# RGB_CCM.net
KiCad netlist of a schematic drawn in Altium Designer
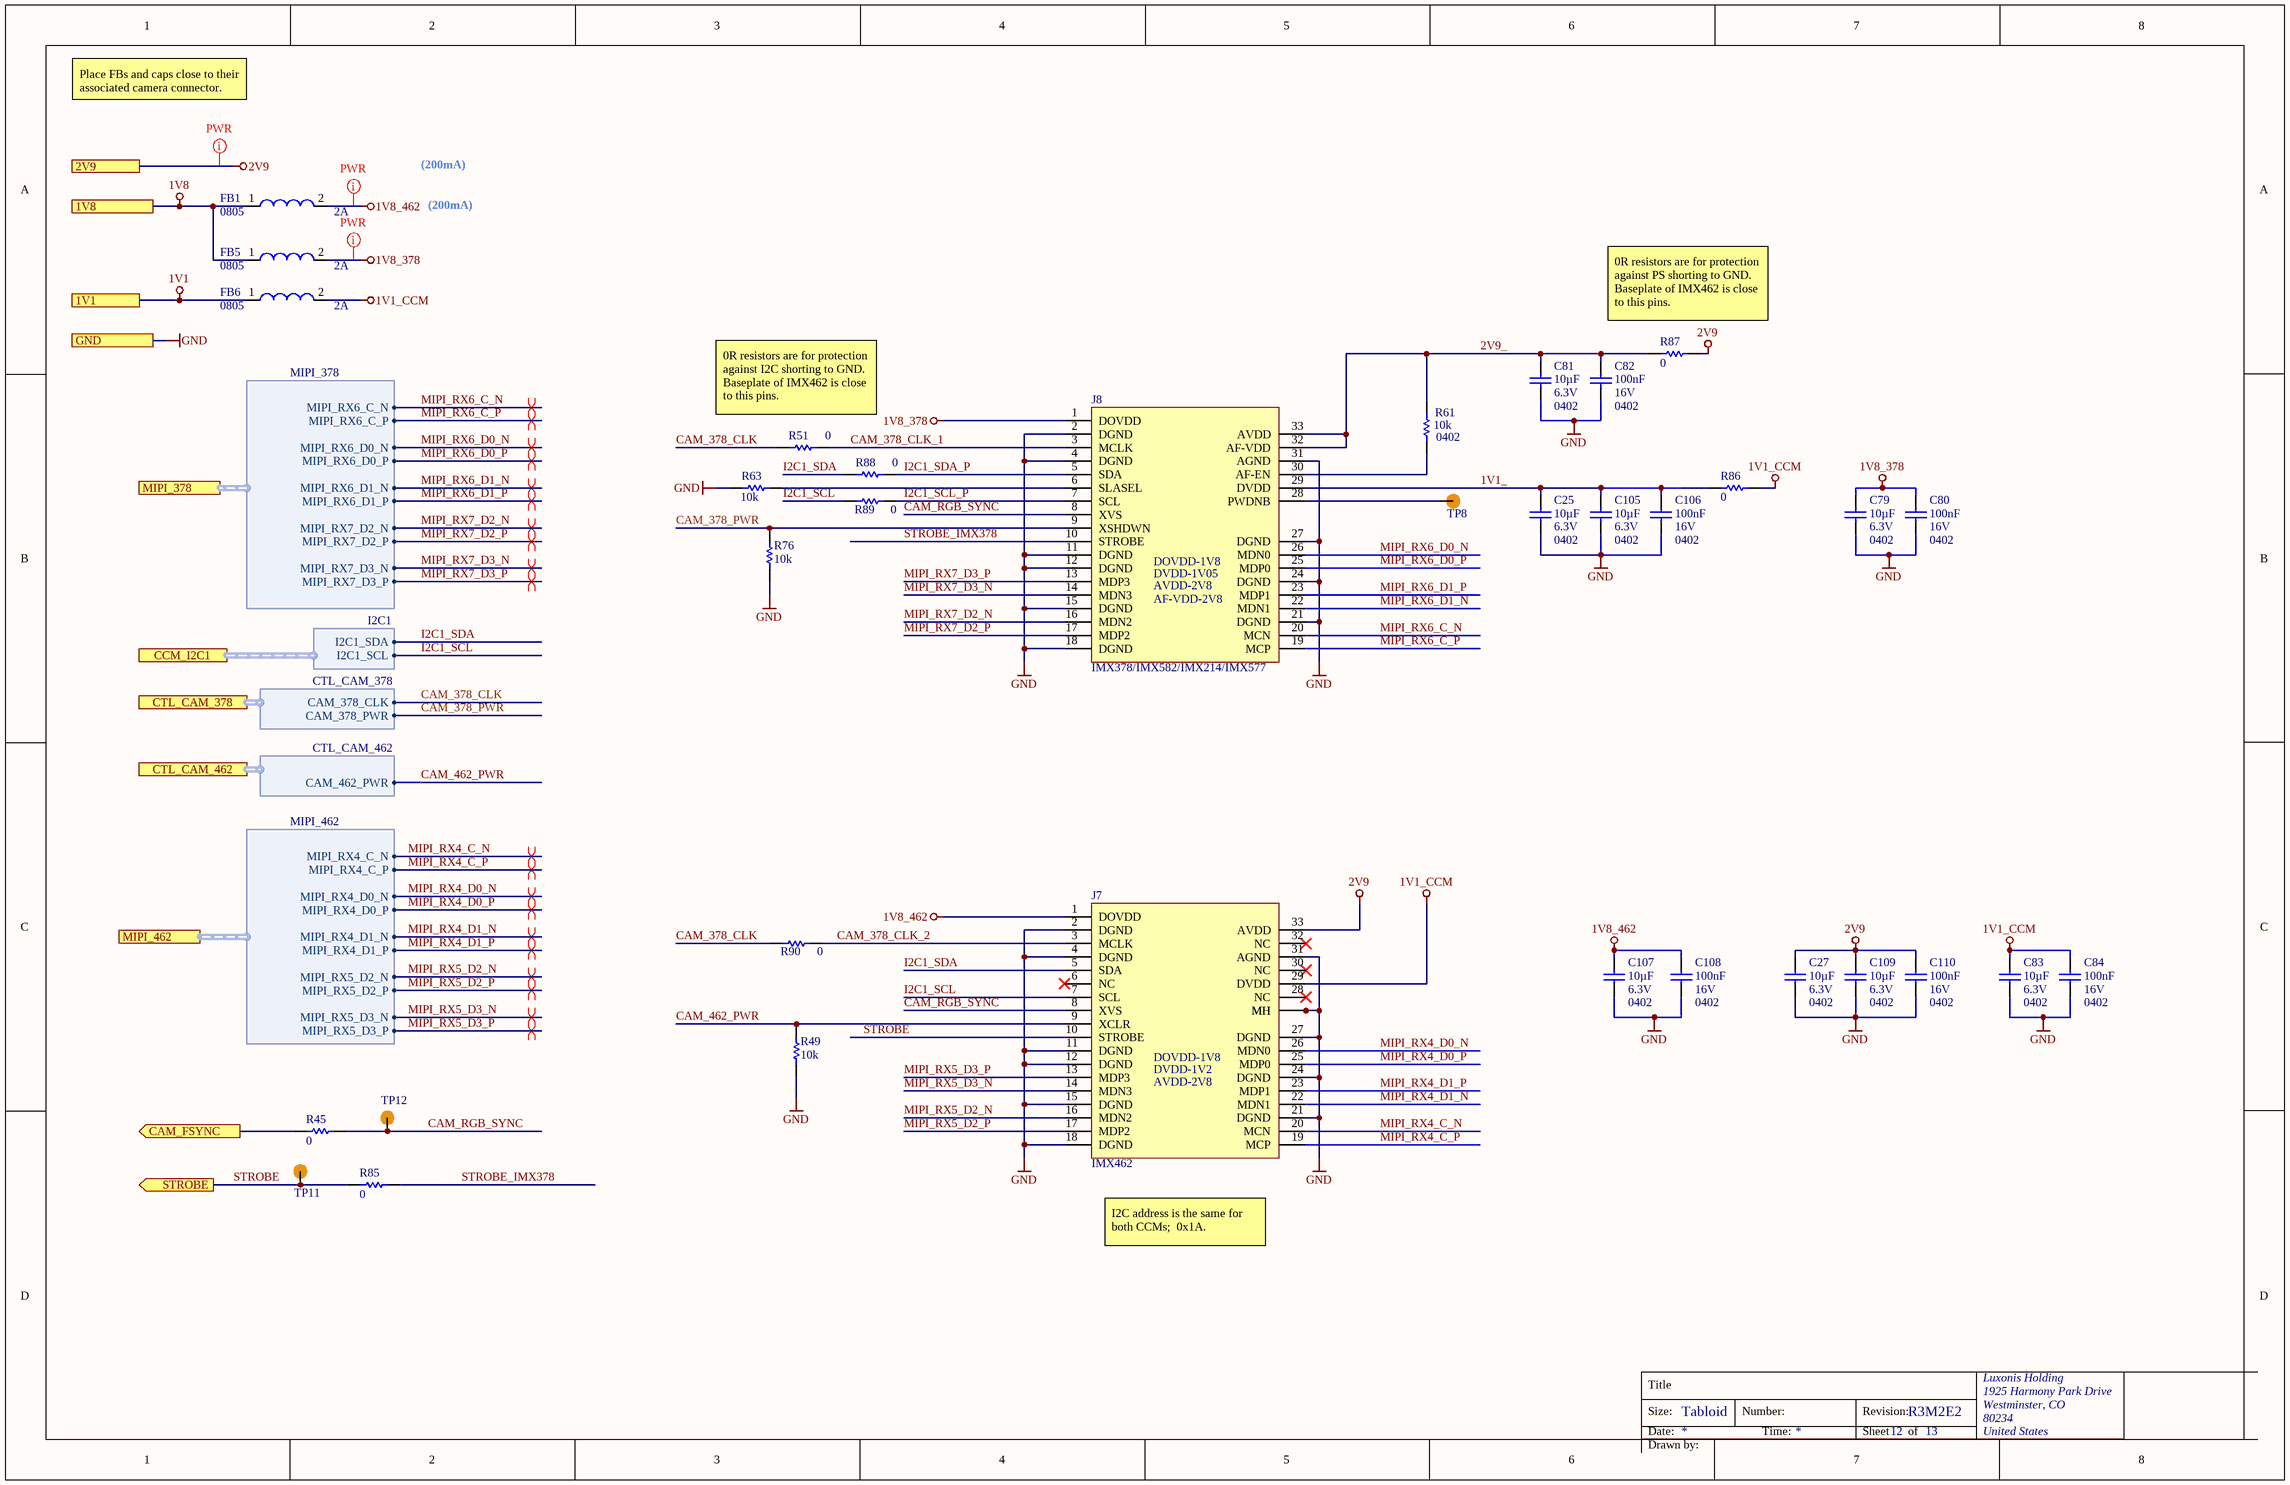
[diagram p0: RGB_CCM.SchDoc]

(export (version "E")
  (design (tool "Eeschema 10.0.6"))
  (components
    (comp (ref "C25")
      (value "10µF")
      (footprint "CAPC0402(1005)70_L")
      (description "CAP CER 10UF 6.3V X5R 0402 20%")
      (fields
        (field (name "VOLTAGE RATING") "6.3V")
        (field (name "CASE/PACKAGE") "0402")
        (field (name "TOLERANCE") "20%")
        (field (name "Comment") "GRM155R60J106ME15D")
      )
      (libsource (lib "Luxonis LLC") (part "LLL153C70G474ME17E"))
    )
    (comp (ref "C27")
      (value "10µF")
      (footprint "CAPC0402(1005)70_L")
      (description "CAP CER 10UF 6.3V X5R 0402 20%")
      (fields
        (field (name "VOLTAGE RATING") "6.3V")
        (field (name "CASE/PACKAGE") "0402")
        (field (name "TOLERANCE") "20%")
        (field (name "Comment") "GRM155R60J106ME15D")
      )
      (libsource (lib "Luxonis LLC") (part "LLL153C70G474ME17E"))
    )
    (comp (ref "C79")
      (value "10µF")
      (footprint "CAPC0402(1005)70_L")
      (description "CAP CER 10UF 6.3V X5R 0402 20%")
      (fields
        (field (name "VOLTAGE RATING") "6.3V")
        (field (name "CASE/PACKAGE") "0402")
        (field (name "TOLERANCE") "20%")
        (field (name "Comment") "GRM155R60J106ME15D")
      )
      (libsource (lib "Luxonis LLC") (part "LLL153C70G474ME17E"))
    )
    (comp (ref "C80")
      (value "100nF")
      (footprint "CAPC0402(1005)60_L")
      (description "CAP CER 0.1UF 16V X7R 0402 10%")
      (fields
        (field (name "VOLTAGE RATING") "16V")
        (field (name "CASE/PACKAGE") "0402")
        (field (name "TOLERANCE") "10%")
        (field (name "Comment") "CL05B104KO5NFNC")
      )
      (libsource (lib "Luxonis LLC") (part "GRM188R61C475KAAJD"))
    )
    (comp (ref "C81")
      (value "10µF")
      (footprint "CAPC0402(1005)70_L")
      (description "CAP CER 10UF 6.3V X5R 0402 20%")
      (fields
        (field (name "VOLTAGE RATING") "6.3V")
        (field (name "CASE/PACKAGE") "0402")
        (field (name "TOLERANCE") "20%")
        (field (name "Comment") "GRM155R60J106ME15D")
      )
      (libsource (lib "Luxonis LLC") (part "LLL153C70G474ME17E"))
    )
    (comp (ref "C82")
      (value "100nF")
      (footprint "CAPC0402(1005)60_L")
      (description "CAP CER 0.1UF 16V X7R 0402 10%")
      (fields
        (field (name "VOLTAGE RATING") "16V")
        (field (name "CASE/PACKAGE") "0402")
        (field (name "TOLERANCE") "10%")
        (field (name "Comment") "CL05B104KO5NFNC")
      )
      (libsource (lib "Luxonis LLC") (part "GRM188R61C475KAAJD"))
    )
    (comp (ref "C83")
      (value "10µF")
      (footprint "CAPC0402(1005)70_L")
      (description "CAP CER 10UF 6.3V X5R 0402 20%")
      (fields
        (field (name "VOLTAGE RATING") "6.3V")
        (field (name "CASE/PACKAGE") "0402")
        (field (name "TOLERANCE") "20%")
        (field (name "Comment") "GRM155R60J106ME15D")
      )
      (libsource (lib "Luxonis LLC") (part "LLL153C70G474ME17E"))
    )
    (comp (ref "C84")
      (value "100nF")
      (footprint "CAPC0402(1005)60_L")
      (description "CAP CER 0.1UF 16V X7R 0402 10%")
      (fields
        (field (name "VOLTAGE RATING") "16V")
        (field (name "CASE/PACKAGE") "0402")
        (field (name "TOLERANCE") "10%")
        (field (name "Comment") "CL05B104KO5NFNC")
      )
      (libsource (lib "Luxonis LLC") (part "GRM188R61C475KAAJD"))
    )
    (comp (ref "C105")
      (value "10µF")
      (footprint "CAPC0402(1005)70_L")
      (description "CAP CER 10UF 6.3V X5R 0402 20%")
      (fields
        (field (name "VOLTAGE RATING") "6.3V")
        (field (name "CASE/PACKAGE") "0402")
        (field (name "TOLERANCE") "20%")
        (field (name "Comment") "GRM155R60J106ME15D")
      )
      (libsource (lib "Luxonis LLC") (part "LLL153C70G474ME17E"))
    )
    (comp (ref "C106")
      (value "100nF")
      (footprint "CAPC0402(1005)60_L")
      (description "CAP CER 0.1UF 16V X7R 0402 10%")
      (fields
        (field (name "VOLTAGE RATING") "16V")
        (field (name "CASE/PACKAGE") "0402")
        (field (name "TOLERANCE") "10%")
        (field (name "Comment") "CL05B104KO5NFNC")
      )
      (libsource (lib "Luxonis LLC") (part "GRM188R61C475KAAJD"))
    )
    (comp (ref "C107")
      (value "10µF")
      (footprint "CAPC0402(1005)70_L")
      (description "CAP CER 10UF 6.3V X5R 0402 20%")
      (fields
        (field (name "VOLTAGE RATING") "6.3V")
        (field (name "CASE/PACKAGE") "0402")
        (field (name "TOLERANCE") "20%")
        (field (name "Comment") "GRM155R60J106ME15D")
      )
      (libsource (lib "Luxonis LLC") (part "LLL153C70G474ME17E"))
    )
    (comp (ref "C108")
      (value "100nF")
      (footprint "CAPC0402(1005)60_L")
      (description "CAP CER 0.1UF 16V X7R 0402 10%")
      (fields
        (field (name "VOLTAGE RATING") "16V")
        (field (name "CASE/PACKAGE") "0402")
        (field (name "TOLERANCE") "10%")
        (field (name "Comment") "CL05B104KO5NFNC")
      )
      (libsource (lib "Luxonis LLC") (part "GRM188R61C475KAAJD"))
    )
    (comp (ref "C109")
      (value "10µF")
      (footprint "CAPC0402(1005)70_L")
      (description "CAP CER 10UF 6.3V X5R 0402 20%")
      (fields
        (field (name "VOLTAGE RATING") "6.3V")
        (field (name "CASE/PACKAGE") "0402")
        (field (name "TOLERANCE") "20%")
        (field (name "Comment") "GRM155R60J106ME15D")
      )
      (libsource (lib "Luxonis LLC") (part "LLL153C70G474ME17E"))
    )
    (comp (ref "C110")
      (value "100nF")
      (footprint "CAPC0402(1005)60_L")
      (description "CAP CER 0.1UF 16V X7R 0402 10%")
      (fields
        (field (name "VOLTAGE RATING") "16V")
        (field (name "CASE/PACKAGE") "0402")
        (field (name "TOLERANCE") "10%")
        (field (name "Comment") "CL05B104KO5NFNC")
      )
      (libsource (lib "Luxonis LLC") (part "GRM188R61C475KAAJD"))
    )
    (comp (ref "FB1")
      (value "2508056017Y2")
      (footprint "2508056017Y2")
      (description "FERRITE BEAD, 0.1OHM, 2A, 0805, 600R/100MHz")
      (fields
        (field (name "CURRENT RATING") "2A")
        (field (name "CASE/PACKAGE") "0805")
        (field (name "TOLERANCE") "25%")
      )
      (libsource (lib "Luxonis LLC") (part "2508056017Y2"))
    )
    (comp (ref "FB5")
      (value "2508056017Y2")
      (footprint "2508056017Y2")
      (description "FERRITE BEAD, 0.1OHM, 2A, 0805, 600R/100MHz")
      (fields
        (field (name "CURRENT RATING") "2A")
        (field (name "CASE/PACKAGE") "0805")
        (field (name "TOLERANCE") "25%")
      )
      (libsource (lib "Luxonis LLC") (part "2508056017Y2"))
    )
    (comp (ref "FB6")
      (value "2508056017Y2")
      (footprint "2508056017Y2")
      (description "FERRITE BEAD, 0.1OHM, 2A, 0805, 600R/100MHz")
      (fields
        (field (name "CURRENT RATING") "2A")
        (field (name "CASE/PACKAGE") "0805")
        (field (name "TOLERANCE") "25%")
      )
      (libsource (lib "Luxonis LLC") (part "2508056017Y2"))
    )
    (comp (ref "J7")
      (value "IMX462")
      (footprint "AC_PY154-IMX462_CON")
      (description "FFC/FPC Connector, 33 Contact(s), 1 Row(s), Female, Right Angle, Surface Mount Terminal")
      (libsource (lib "Luxonis LLC") (part "AC_PY154-IMX462_CON"))
    )
    (comp (ref "J8")
      (value "IMX378/IMX582/IMX214/IMX577")
      (footprint "PY004")
      (description "FFC/FPC Connector, 33 Contact(s), 1 Row(s), Female, Right Angle, Surface Mount Terminal")
      (libsource (lib "Luxonis LLC") (part "IMX378/IMX582"))
    )
    (comp (ref "R45")
      (value "0")
      (footprint "RESC0402(1005)_L")
      (description "RES SMD 0 OHM 5% 1/16W 0402")
      (fields (field (name "TOLERANCE") "5%"))
      (libsource (lib "Luxonis LLC") (part "Default resistor symbol"))
    )
    (comp (ref "R49")
      (value "10k")
      (footprint "RESC0402(1005)_N")
      (description "RES SMD 10K OHM 1% 1/16W 0402")
      (fields (field (name "TOLERANCE") "1%") (field (name "Comment") "RC0402FR-1310KL"))
      (libsource (lib "Luxonis LLC") (part "RC0402FR-0722RL_1"))
    )
    (comp (ref "R51")
      (value "0")
      (footprint "RESC0402(1005)_L")
      (description "RES SMD 0 OHM 5% 1/16W 0402")
      (fields (field (name "TOLERANCE") "5%"))
      (libsource (lib "Luxonis LLC") (part "Default resistor symbol"))
    )
    (comp (ref "R61")
      (value "10k")
      (footprint "RESC0402(1005)_N")
      (description "RES SMD 10K OHM 1% 1/16W 0402")
      (fields
        (field (name "CASE/PACKAGE") "0402")
        (field (name "TOLERANCE") "1%")
        (field (name "Comment") "RC0402FR-1310KL")
      )
      (libsource (lib "Luxonis LLC") (part "RC0402FR-0722RL_1"))
    )
    (comp (ref "R63")
      (value "10k")
      (footprint "RESC0402(1005)_N")
      (description "RES SMD 10K OHM 1% 1/16W 0402")
      (fields (field (name "TOLERANCE") "1%") (field (name "Comment") "RC0402FR-1310KL"))
      (libsource (lib "Luxonis LLC") (part "RC0402FR-0722RL_1"))
    )
    (comp (ref "R76")
      (value "10k")
      (footprint "RESC0402(1005)_N")
      (description "RES SMD 10K OHM 1% 1/16W 0402")
      (fields (field (name "TOLERANCE") "1%") (field (name "Comment") "RC0402FR-1310KL"))
      (libsource (lib "Luxonis LLC") (part "RC0402FR-0722RL_1"))
    )
    (comp (ref "R85")
      (value "0")
      (footprint "RESC0402(1005)_L")
      (description "RES SMD 0 OHM 5% 1/16W 0402")
      (fields (field (name "TOLERANCE") "5%"))
      (libsource (lib "Luxonis LLC") (part "Default resistor symbol"))
    )
    (comp (ref "R86")
      (value "0")
      (footprint "RESC0402(1005)_L")
      (description "RES SMD 0 OHM 5% 1/16W 0402")
      (fields (field (name "TOLERANCE") "5%"))
      (libsource (lib "Luxonis LLC") (part "Default resistor symbol"))
    )
    (comp (ref "R87")
      (value "0")
      (footprint "RESC0402(1005)_L")
      (description "RES SMD 0 OHM 5% 1/16W 0402")
      (fields (field (name "TOLERANCE") "5%"))
      (libsource (lib "Luxonis LLC") (part "Default resistor symbol"))
    )
    (comp (ref "R88")
      (value "0")
      (footprint "RESC0402(1005)_L")
      (description "RES SMD 0 OHM 5% 1/16W 0402")
      (fields (field (name "TOLERANCE") "5%"))
      (libsource (lib "Luxonis LLC") (part "Default resistor symbol"))
    )
    (comp (ref "R89")
      (value "0")
      (footprint "RESC0402(1005)_L")
      (description "RES SMD 0 OHM 5% 1/16W 0402")
      (fields (field (name "TOLERANCE") "5%"))
      (libsource (lib "Luxonis LLC") (part "Default resistor symbol"))
    )
    (comp (ref "R90")
      (value "0")
      (footprint "RESC0402(1005)_L")
      (description "RES SMD 0 OHM 5% 1/16W 0402")
      (fields (field (name "TOLERANCE") "5%"))
      (libsource (lib "Luxonis LLC") (part "Default resistor symbol"))
    )
    (comp (ref "TP8")
      (value "TEST_POINT")
      (footprint "TP075_150_NS")
      (libsource (lib "Luxonis LLC") (part "TEST_POINT"))
    )
    (comp (ref "TP11")
      (value "TEST_POINT")
      (footprint "TP075_150_NS")
      (libsource (lib "Luxonis LLC") (part "TEST_POINT"))
    )
    (comp (ref "TP12")
      (value "TEST_POINT")
      (footprint "TP075_150_NS")
      (libsource (lib "Luxonis LLC") (part "TEST_POINT"))
    )
  )
  (nets
    (net (code "6") (name "/1V1_") (class "Default")
      (node (ref "C105") (pin "2") (pinfunction "2_2") (pintype "passive"))
      (node (ref "C106") (pin "2") (pinfunction "2_2") (pintype "passive"))
      (node (ref "C25") (pin "2") (pinfunction "2_2") (pintype "passive"))
      (node (ref "J8") (pin "29") (pinfunction "DVDD_29") (pintype "passive"))
      (node (ref "R86") (pin "2") (pinfunction "2_2") (pintype "passive"))
    )
    (net (code "7") (name "/2V9_") (class "Default")
      (node (ref "C81") (pin "2") (pinfunction "2_2") (pintype "passive"))
      (node (ref "C82") (pin "2") (pinfunction "2_2") (pintype "passive"))
      (node (ref "J8") (pin "32") (pinfunction "AF-VDD_32") (pintype "passive"))
      (node (ref "J8") (pin "33") (pinfunction "AVDD_33") (pintype "passive"))
      (node (ref "R61") (pin "2") (pinfunction "2_2") (pintype "passive"))
      (node (ref "R87") (pin "2") (pinfunction "2_2") (pintype "passive"))
    )
    (net (code "8") (name "/CAM_378_CLK") (class "Default")
      (node (ref "R51") (pin "2") (pinfunction "2_2") (pintype "passive"))
      (node (ref "R90") (pin "2") (pinfunction "2_2") (pintype "passive"))
    )
    (net (code "9") (name "/CAM_378_CLK_1") (class "Default")
      (node (ref "J8") (pin "3") (pinfunction "MCLK_3") (pintype "passive"))
      (node (ref "R51") (pin "1") (pinfunction "1_1") (pintype "passive"))
    )
    (net (code "10") (name "/CAM_378_CLK_2") (class "Default")
      (node (ref "J7") (pin "3") (pinfunction "MCLK_3") (pintype "passive"))
      (node (ref "R90") (pin "1") (pinfunction "1_1") (pintype "passive"))
    )
    (net (code "11") (name "/CAM_378_PWR") (class "Default")
      (node (ref "J8") (pin "9") (pinfunction "XSHDWN_9") (pintype "passive"))
      (node (ref "R76") (pin "1") (pinfunction "1_1") (pintype "passive"))
    )
    (net (code "12") (name "/CAM_462_PWR") (class "Default")
      (node (ref "J7") (pin "9") (pinfunction "XCLR_9") (pintype "passive"))
      (node (ref "R49") (pin "1") (pinfunction "1_1") (pintype "passive"))
    )
    (net (code "13") (name "/CAM_FSYNC") (class "Default")
      (node (ref "R45") (pin "2") (pinfunction "2_2") (pintype "passive"))
    )
    (net (code "14") (name "/CAM_RGB_SYNC") (class "Default")
      (node (ref "J7") (pin "8") (pinfunction "XVS_8") (pintype "passive"))
      (node (ref "J8") (pin "8") (pinfunction "XVS_8") (pintype "passive"))
      (node (ref "R45") (pin "1") (pinfunction "1_1") (pintype "passive"))
      (node (ref "TP12") (pin "1") (pintype "passive"))
    )
    (net (code "15") (name "/I2C1_SCL") (class "Default")
      (node (ref "J7") (pin "7") (pinfunction "SCL_7") (pintype "passive"))
      (node (ref "R89") (pin "2") (pinfunction "2_2") (pintype "passive"))
    )
    (net (code "16") (name "/I2C1_SCL_P") (class "Default")
      (node (ref "J8") (pin "7") (pinfunction "SCL_7") (pintype "passive"))
      (node (ref "R89") (pin "1") (pinfunction "1_1") (pintype "passive"))
    )
    (net (code "17") (name "/I2C1_SDA") (class "Default")
      (node (ref "J7") (pin "5") (pinfunction "SDA_5") (pintype "passive"))
      (node (ref "R88") (pin "2") (pinfunction "2_2") (pintype "passive"))
    )
    (net (code "18") (name "/I2C1_SDA_P") (class "Default")
      (node (ref "J8") (pin "5") (pinfunction "SDA_5") (pintype "passive"))
      (node (ref "R88") (pin "1") (pinfunction "1_1") (pintype "passive"))
    )
    (net (code "19") (name "/MIPI_RX4_C_N") (class "Default")
      (node (ref "J7") (pin "20") (pinfunction "MCN_20") (pintype "passive"))
    )
    (net (code "20") (name "/MIPI_RX4_C_P") (class "Default")
      (node (ref "J7") (pin "19") (pinfunction "MCP_19") (pintype "passive"))
    )
    (net (code "21") (name "/MIPI_RX4_D0_N") (class "Default")
      (node (ref "J7") (pin "26") (pinfunction "MDN0_26") (pintype "passive"))
    )
    (net (code "22") (name "/MIPI_RX4_D0_P") (class "Default")
      (node (ref "J7") (pin "25") (pinfunction "MDP0_25") (pintype "passive"))
    )
    (net (code "23") (name "/MIPI_RX4_D1_N") (class "Default")
      (node (ref "J7") (pin "22") (pinfunction "MDN1_22") (pintype "passive"))
    )
    (net (code "24") (name "/MIPI_RX4_D1_P") (class "Default")
      (node (ref "J7") (pin "23") (pinfunction "MDP1_23") (pintype "passive"))
    )
    (net (code "25") (name "/MIPI_RX5_D2_N") (class "Default")
      (node (ref "J7") (pin "16") (pinfunction "MDN2_16") (pintype "passive"))
    )
    (net (code "26") (name "/MIPI_RX5_D2_P") (class "Default")
      (node (ref "J7") (pin "17") (pinfunction "MDP2_17") (pintype "passive"))
    )
    (net (code "27") (name "/MIPI_RX5_D3_N") (class "Default")
      (node (ref "J7") (pin "14") (pinfunction "MDN3_14") (pintype "passive"))
    )
    (net (code "28") (name "/MIPI_RX5_D3_P") (class "Default")
      (node (ref "J7") (pin "13") (pinfunction "MDP3_13") (pintype "passive"))
    )
    (net (code "29") (name "/MIPI_RX6_C_N") (class "Default")
      (node (ref "J8") (pin "20") (pinfunction "MCN_20") (pintype "passive"))
    )
    (net (code "30") (name "/MIPI_RX6_C_P") (class "Default")
      (node (ref "J8") (pin "19") (pinfunction "MCP_19") (pintype "passive"))
    )
    (net (code "31") (name "/MIPI_RX6_D0_N") (class "Default")
      (node (ref "J8") (pin "26") (pinfunction "MDN0_26") (pintype "passive"))
    )
    (net (code "32") (name "/MIPI_RX6_D0_P") (class "Default")
      (node (ref "J8") (pin "25") (pinfunction "MDP0_25") (pintype "passive"))
    )
    (net (code "33") (name "/MIPI_RX6_D1_N") (class "Default")
      (node (ref "J8") (pin "22") (pinfunction "MDN1_22") (pintype "passive"))
    )
    (net (code "34") (name "/MIPI_RX6_D1_P") (class "Default")
      (node (ref "J8") (pin "23") (pinfunction "MDP1_23") (pintype "passive"))
    )
    (net (code "35") (name "/MIPI_RX7_D2_N") (class "Default")
      (node (ref "J8") (pin "16") (pinfunction "MDN2_16") (pintype "passive"))
    )
    (net (code "36") (name "/MIPI_RX7_D2_P") (class "Default")
      (node (ref "J8") (pin "17") (pinfunction "MDP2_17") (pintype "passive"))
    )
    (net (code "37") (name "/MIPI_RX7_D3_N") (class "Default")
      (node (ref "J8") (pin "14") (pinfunction "MDN3_14") (pintype "passive"))
    )
    (net (code "38") (name "/MIPI_RX7_D3_P") (class "Default")
      (node (ref "J8") (pin "13") (pinfunction "MDP3_13") (pintype "passive"))
    )
    (net (code "39") (name "/STROBE") (class "Default")
      (node (ref "J7") (pin "10") (pinfunction "STROBE_10") (pintype "passive"))
      (node (ref "R85") (pin "2") (pinfunction "2_2") (pintype "passive"))
      (node (ref "TP11") (pin "1") (pintype "passive"))
    )
    (net (code "40") (name "/STROBE_IMX378") (class "Default")
      (node (ref "J8") (pin "10") (pinfunction "STROBE_10") (pintype "passive"))
      (node (ref "R85") (pin "1") (pinfunction "1_1") (pintype "passive"))
    )
    (net (code "46") (name "1V1") (class "Default")
      (node (ref "FB6") (pin "1") (pinfunction "1_1") (pintype "passive"))
    )
    (net (code "47") (name "1V1_CCM") (class "Default")
      (node (ref "C83") (pin "2") (pinfunction "2_2") (pintype "passive"))
      (node (ref "C84") (pin "2") (pinfunction "2_2") (pintype "passive"))
      (node (ref "FB6") (pin "2") (pinfunction "2_2") (pintype "passive"))
      (node (ref "J7") (pin "29") (pinfunction "DVDD_29") (pintype "passive"))
      (node (ref "R86") (pin "1") (pinfunction "1_1") (pintype "passive"))
    )
    (net (code "48") (name "1V8") (class "Default")
      (node (ref "FB1") (pin "1") (pinfunction "1_1") (pintype "passive"))
      (node (ref "FB5") (pin "1") (pinfunction "1_1") (pintype "passive"))
    )
    (net (code "49") (name "1V8_378") (class "Default")
      (node (ref "C79") (pin "2") (pinfunction "2_2") (pintype "passive"))
      (node (ref "C80") (pin "2") (pinfunction "2_2") (pintype "passive"))
      (node (ref "FB5") (pin "2") (pinfunction "2_2") (pintype "passive"))
      (node (ref "J8") (pin "1") (pinfunction "DOVDD_1") (pintype "passive"))
    )
    (net (code "50") (name "1V8_462") (class "Default")
      (node (ref "C107") (pin "2") (pinfunction "2_2") (pintype "passive"))
      (node (ref "C108") (pin "2") (pinfunction "2_2") (pintype "passive"))
      (node (ref "FB1") (pin "2") (pinfunction "2_2") (pintype "passive"))
      (node (ref "J7") (pin "1") (pinfunction "DOVDD_1") (pintype "passive"))
    )
    (net (code "51") (name "2V9") (class "Default")
      (node (ref "C109") (pin "2") (pinfunction "2_2") (pintype "passive"))
      (node (ref "C110") (pin "2") (pinfunction "2_2") (pintype "passive"))
      (node (ref "C27") (pin "2") (pinfunction "2_2") (pintype "passive"))
      (node (ref "J7") (pin "33") (pinfunction "AVDD_33") (pintype "passive"))
      (node (ref "R87") (pin "1") (pinfunction "1_1") (pintype "passive"))
    )
    (net (code "52") (name "GND") (class "Default")
      (node (ref "C105") (pin "1") (pinfunction "1_1") (pintype "passive"))
      (node (ref "C106") (pin "1") (pinfunction "1_1") (pintype "passive"))
      (node (ref "C107") (pin "1") (pinfunction "1_1") (pintype "passive"))
      (node (ref "C108") (pin "1") (pinfunction "1_1") (pintype "passive"))
      (node (ref "C109") (pin "1") (pinfunction "1_1") (pintype "passive"))
      (node (ref "C110") (pin "1") (pinfunction "1_1") (pintype "passive"))
      (node (ref "C25") (pin "1") (pinfunction "1_1") (pintype "passive"))
      (node (ref "C27") (pin "1") (pinfunction "1_1") (pintype "passive"))
      (node (ref "C79") (pin "1") (pinfunction "1_1") (pintype "passive"))
      (node (ref "C80") (pin "1") (pinfunction "1_1") (pintype "passive"))
      (node (ref "C81") (pin "1") (pinfunction "1_1") (pintype "passive"))
      (node (ref "C82") (pin "1") (pinfunction "1_1") (pintype "passive"))
      (node (ref "C83") (pin "1") (pinfunction "1_1") (pintype "passive"))
      (node (ref "C84") (pin "1") (pinfunction "1_1") (pintype "passive"))
      (node (ref "J7") (pin "11") (pinfunction "DGND_11") (pintype "passive"))
      (node (ref "J7") (pin "12") (pinfunction "DGND_12") (pintype "passive"))
      (node (ref "J7") (pin "15") (pinfunction "DGND_15") (pintype "passive"))
      (node (ref "J7") (pin "18") (pinfunction "DGND_18") (pintype "passive"))
      (node (ref "J7") (pin "2") (pinfunction "DGND_2") (pintype "passive"))
      (node (ref "J7") (pin "21") (pinfunction "DGND_21") (pintype "passive"))
      (node (ref "J7") (pin "24") (pinfunction "DGND_24") (pintype "passive"))
      (node (ref "J7") (pin "27") (pinfunction "DGND_27") (pintype "passive"))
      (node (ref "J7") (pin "31") (pinfunction "AGND_31") (pintype "passive"))
      (node (ref "J7") (pin "34") (pinfunction "MH_34") (pintype "passive"))
      (node (ref "J7") (pin "35") (pinfunction "MH_35") (pintype "passive"))
      (node (ref "J7") (pin "4") (pinfunction "DGND_4") (pintype "passive"))
      (node (ref "J8") (pin "11") (pinfunction "DGND_11") (pintype "passive"))
      (node (ref "J8") (pin "12") (pinfunction "DGND_12") (pintype "passive"))
      (node (ref "J8") (pin "15") (pinfunction "DGND_15") (pintype "passive"))
      (node (ref "J8") (pin "18") (pinfunction "DGND_18") (pintype "passive"))
      (node (ref "J8") (pin "2") (pinfunction "DGND_2") (pintype "passive"))
      (node (ref "J8") (pin "21") (pinfunction "DGND_21") (pintype "passive"))
      (node (ref "J8") (pin "24") (pinfunction "DGND_24") (pintype "passive"))
      (node (ref "J8") (pin "27") (pinfunction "DGND_27") (pintype "passive"))
      (node (ref "J8") (pin "31") (pinfunction "AGND_31") (pintype "passive"))
      (node (ref "J8") (pin "4") (pinfunction "DGND_4") (pintype "passive"))
      (node (ref "R49") (pin "2") (pinfunction "2_2") (pintype "passive"))
      (node (ref "R63") (pin "2") (pinfunction "2_2") (pintype "passive"))
      (node (ref "R76") (pin "2") (pinfunction "2_2") (pintype "passive"))
    )
    (net (code "53") (name "Net-(J8-AF-EN)") (class "Default")
      (node (ref "J8") (pin "30") (pinfunction "AF-EN_30") (pintype "passive"))
      (node (ref "R61") (pin "1") (pinfunction "1_1") (pintype "passive"))
    )
    (net (code "54") (name "Net-(J8-PWDNB)") (class "Default")
      (node (ref "J8") (pin "28") (pinfunction "PWDNB_28") (pintype "passive"))
      (node (ref "TP8") (pin "1") (pintype "passive"))
    )
    (net (code "55") (name "Net-(J8-SLASEL)") (class "Default")
      (node (ref "J8") (pin "6") (pinfunction "SLASEL_6") (pintype "passive"))
      (node (ref "R63") (pin "1") (pinfunction "1_1") (pintype "passive"))
    )
    (net (code "56") (name "unconnected-(J7-NC-Pad6)") (class "Default")
      (node (ref "J7") (pin "6") (pinfunction "NC_6") (pintype "passive+no_connect"))
    )
    (net (code "57") (name "unconnected-(J7-NC-Pad28)") (class "Default")
      (node (ref "J7") (pin "28") (pinfunction "NC_28") (pintype "passive+no_connect"))
    )
    (net (code "58") (name "unconnected-(J7-NC-Pad30)") (class "Default")
      (node (ref "J7") (pin "30") (pinfunction "NC_30") (pintype "passive+no_connect"))
    )
    (net (code "59") (name "unconnected-(J7-NC-Pad32)") (class "Default")
      (node (ref "J7") (pin "32") (pinfunction "NC_32") (pintype "passive+no_connect"))
    )
  )
)
